# UDB5-v010.net
KiCad netlist of a schematic drawn in EAGLE
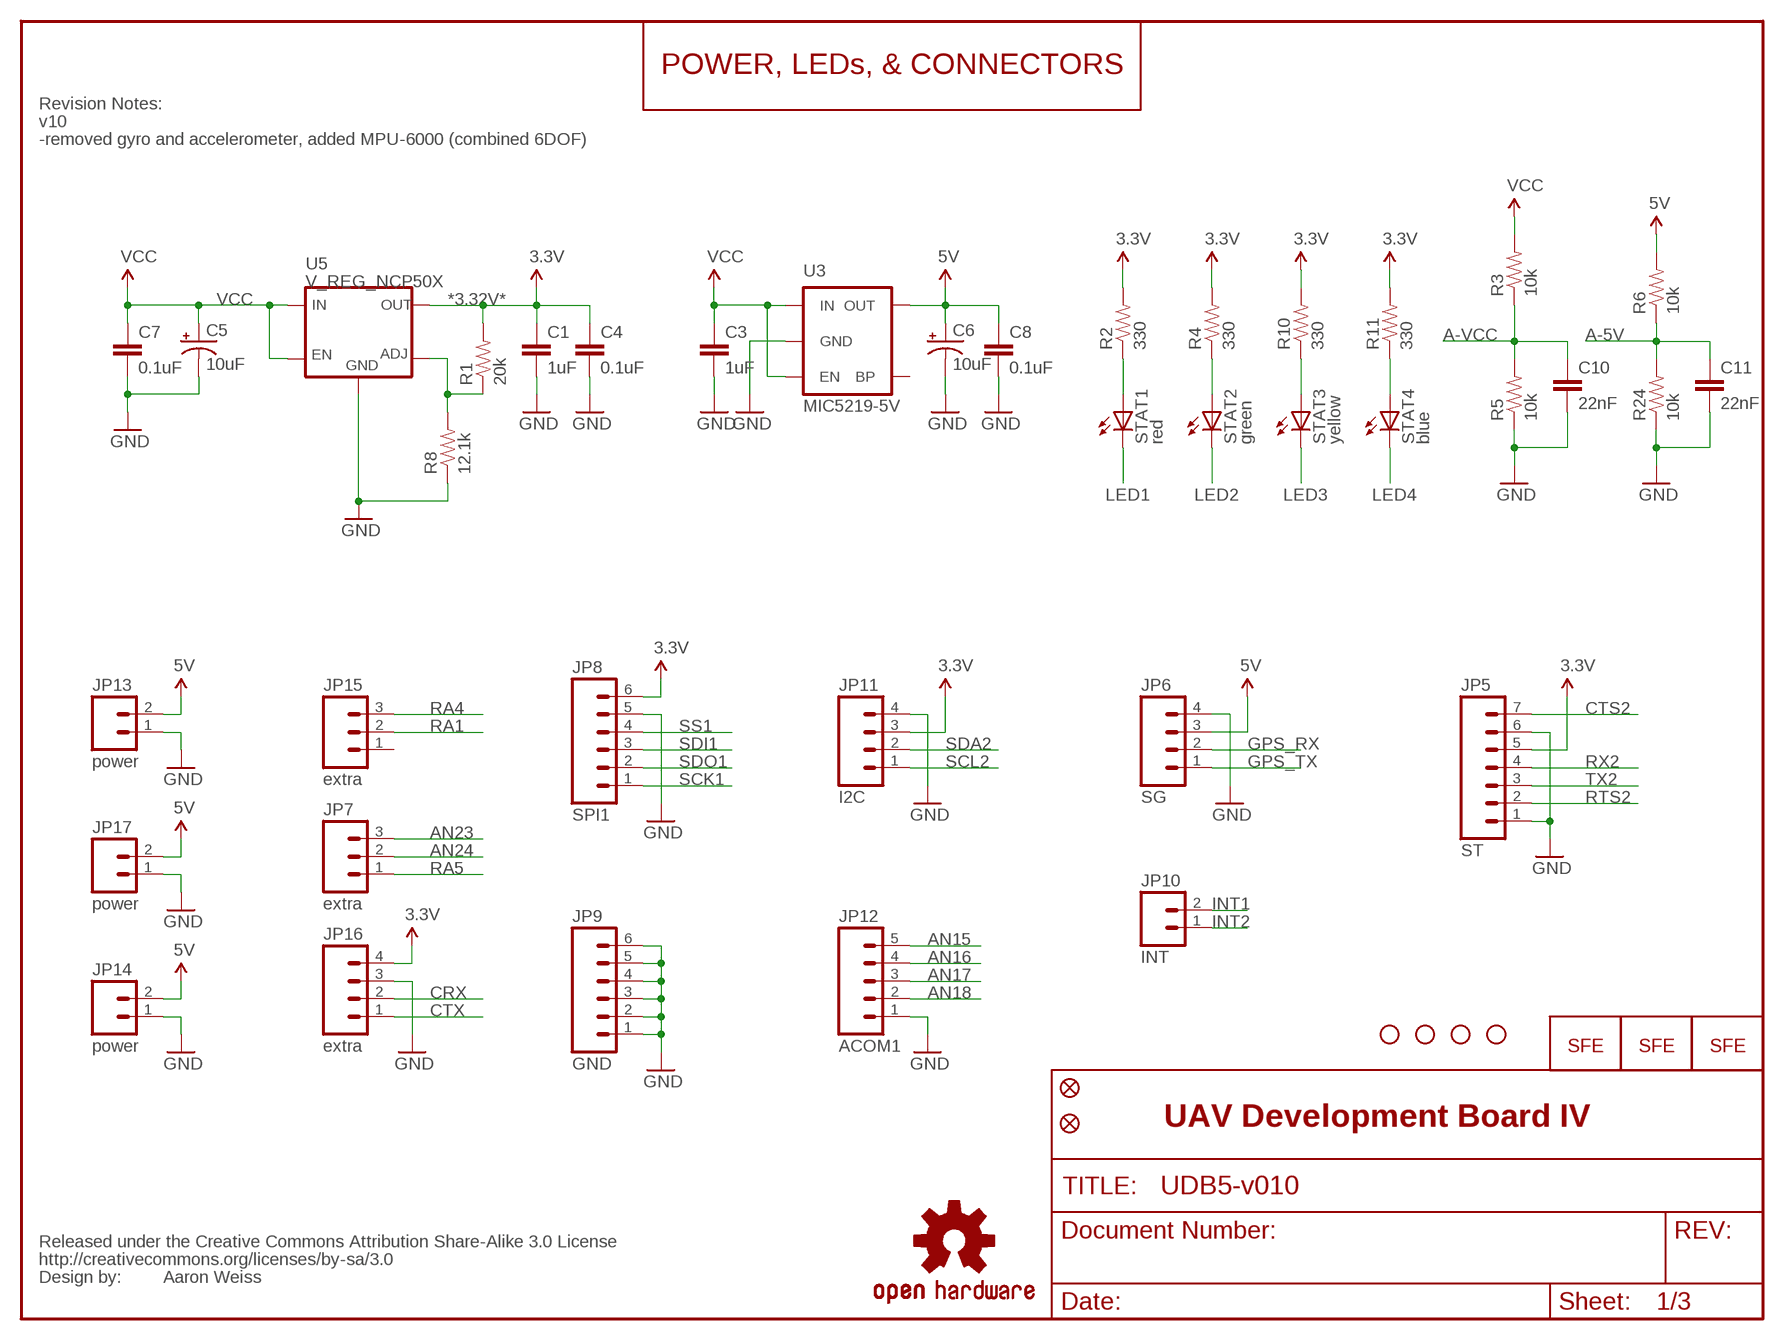
[diagram p0: schematic, sheet 1]
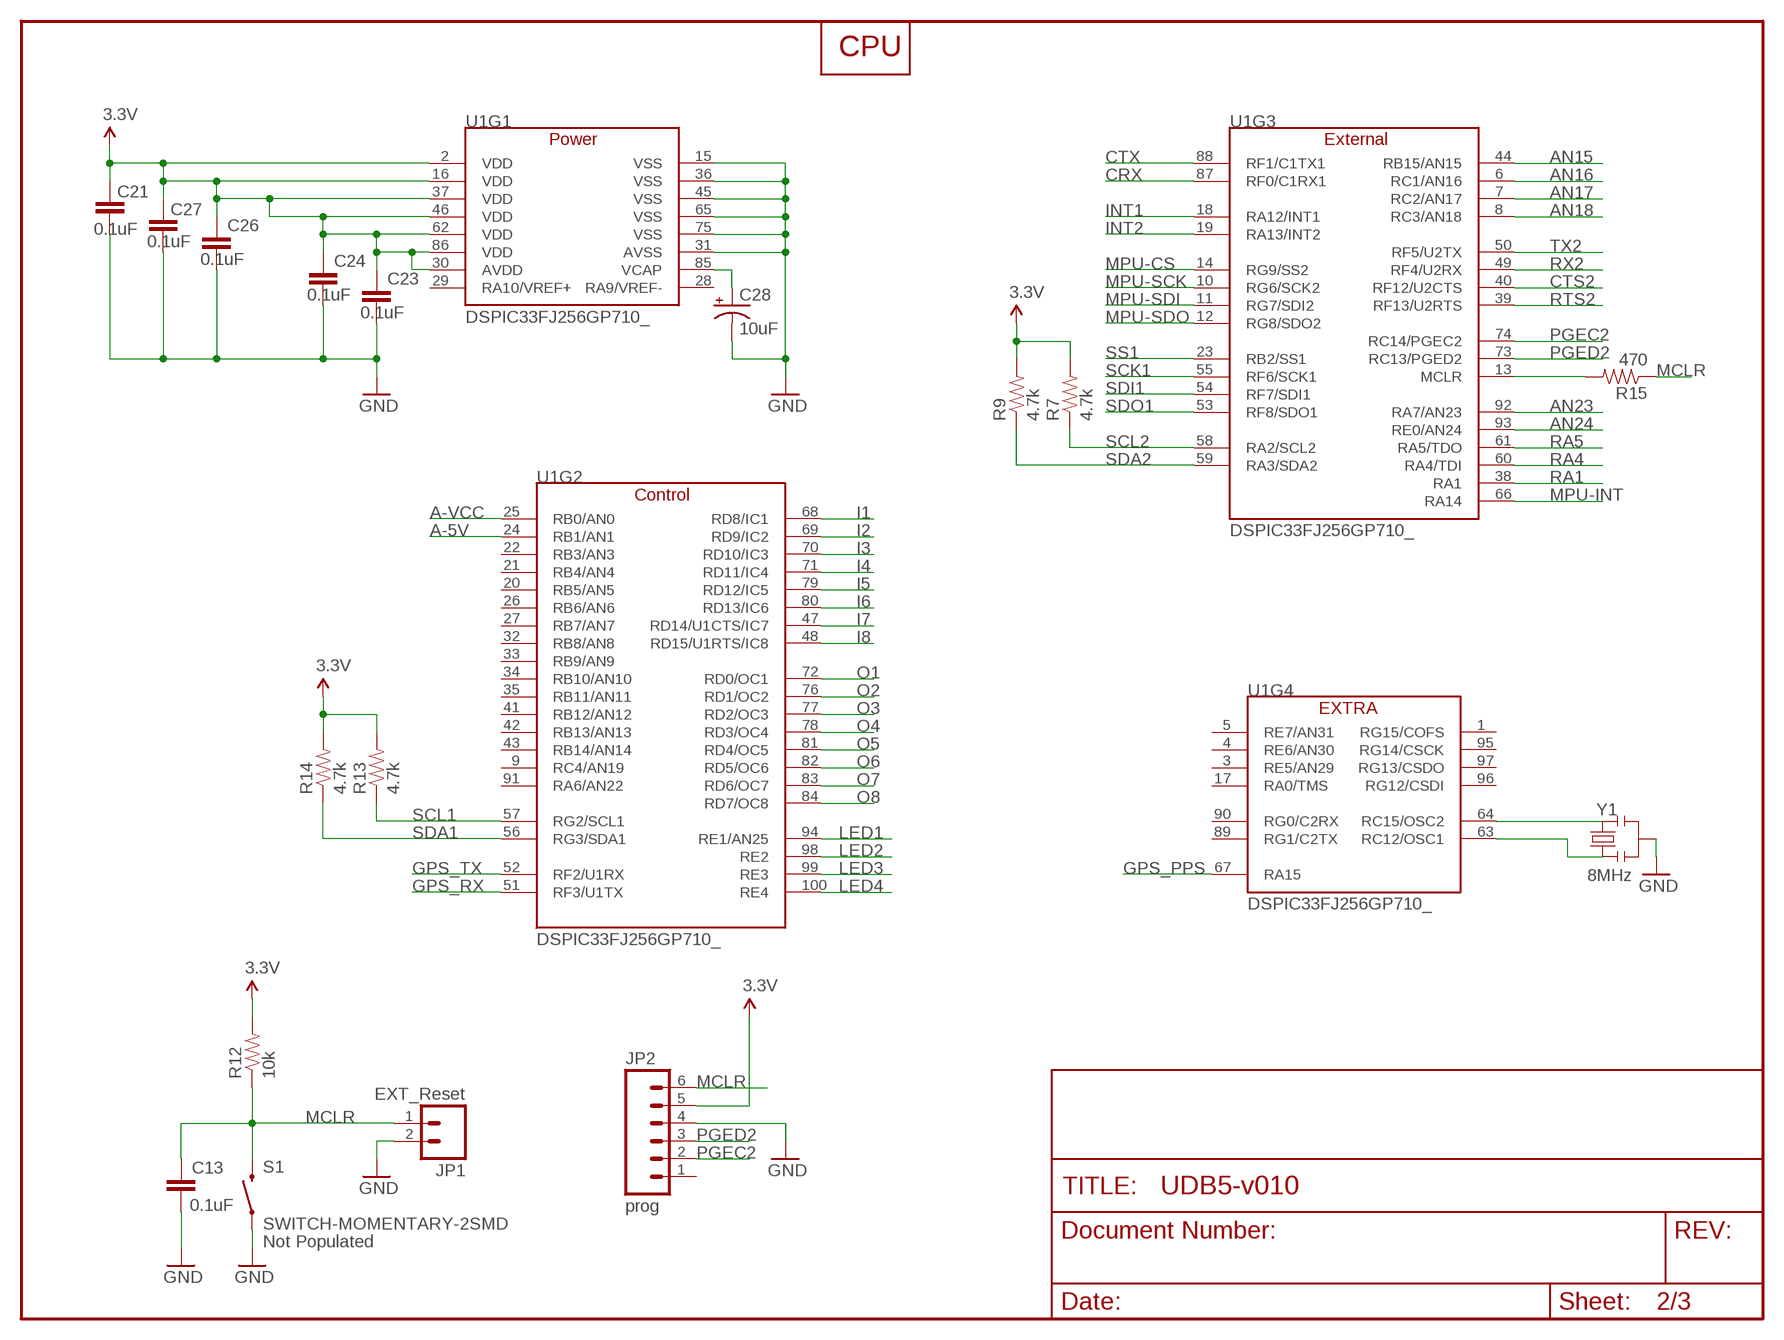
[diagram p1: schematic, sheet 2]
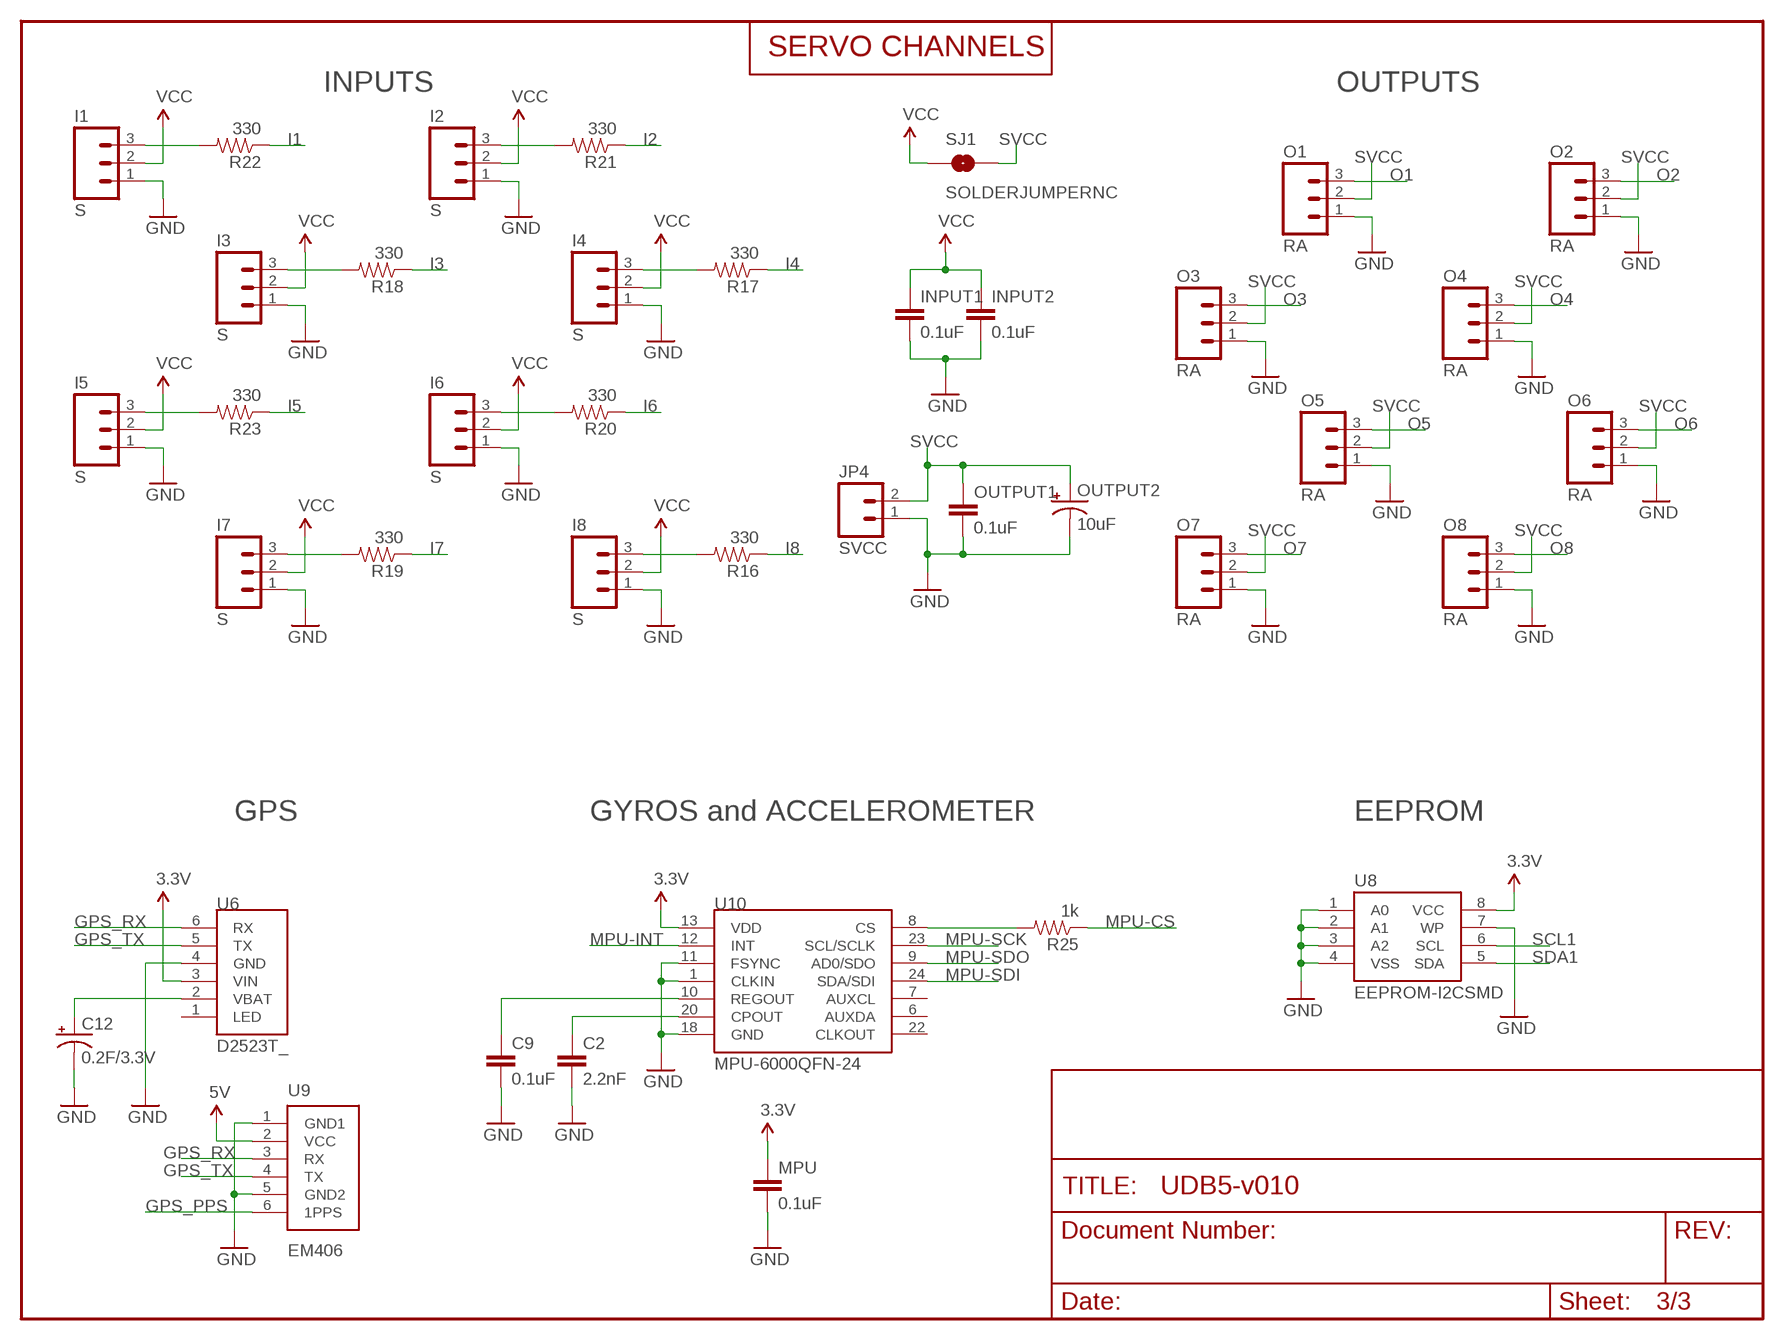
[diagram p2: schematic, sheet 3]

(export (version "E")
  (design (tool "Eeschema 10.0.6"))
  (components
    (comp (ref "C2")
      (value "2.2nF")
      (footprint "eagle-import:0402-CAP")
      (libsource (lib "eagle-import") (part "SparkFun-Capacitors_CAP0402-CAP"))
    )
    (comp (ref "C9")
      (value "0.1uF")
      (footprint "eagle-import:0402-CAP")
      (libsource (lib "eagle-import") (part "SparkFun-Capacitors_CAP0402-CAP"))
    )
    (comp (ref "C12")
      (value "0.2F/3.3V")
      (footprint "eagle-import:EN_J2")
      (libsource (lib "eagle-import") (part "SparkFun-Capacitors_CAP_POLEN_J2"))
    )
    (comp (ref "I1")
      (value "S")
      (footprint "eagle-import:1X03")
      (libsource (lib "eagle-import") (part "M03PTH"))
    )
    (comp (ref "I2")
      (value "S")
      (footprint "eagle-import:1X03")
      (libsource (lib "eagle-import") (part "M03PTH"))
    )
    (comp (ref "I3")
      (value "S")
      (footprint "eagle-import:1X03")
      (libsource (lib "eagle-import") (part "M03PTH"))
    )
    (comp (ref "I4")
      (value "S")
      (footprint "eagle-import:1X03")
      (libsource (lib "eagle-import") (part "M03PTH"))
    )
    (comp (ref "I5")
      (value "S")
      (footprint "eagle-import:1X03")
      (libsource (lib "eagle-import") (part "M03PTH"))
    )
    (comp (ref "I6")
      (value "S")
      (footprint "eagle-import:1X03")
      (libsource (lib "eagle-import") (part "M03PTH"))
    )
    (comp (ref "I7")
      (value "S")
      (footprint "eagle-import:1X03")
      (libsource (lib "eagle-import") (part "M03PTH"))
    )
    (comp (ref "I8")
      (value "S")
      (footprint "eagle-import:1X03")
      (libsource (lib "eagle-import") (part "M03PTH"))
    )
    (comp (ref "INPUT1")
      (value "0.1uF")
      (footprint "eagle-import:0402-CAP")
      (libsource (lib "eagle-import") (part "CAP0402-CAP"))
    )
    (comp (ref "INPUT2")
      (value "0.1uF")
      (footprint "eagle-import:0402-CAP")
      (libsource (lib "eagle-import") (part "CAP0402-CAP"))
    )
    (comp (ref "JP4")
      (value "SVCC")
      (footprint "eagle-import:1X02")
      (libsource (lib "eagle-import") (part "M02PTH"))
    )
    (comp (ref "MPU")
      (value "0.1uF")
      (footprint "eagle-import:0402-CAP")
      (libsource (lib "eagle-import") (part "CAP0402-CAP"))
    )
    (comp (ref "O1")
      (value "RA")
      (footprint "eagle-import:1X03")
      (libsource (lib "eagle-import") (part "M03PTH"))
    )
    (comp (ref "O2")
      (value "RA")
      (footprint "eagle-import:1X03")
      (libsource (lib "eagle-import") (part "M03PTH"))
    )
    (comp (ref "O3")
      (value "RA")
      (footprint "eagle-import:1X03")
      (libsource (lib "eagle-import") (part "M03PTH"))
    )
    (comp (ref "O4")
      (value "RA")
      (footprint "eagle-import:1X03")
      (libsource (lib "eagle-import") (part "M03PTH"))
    )
    (comp (ref "O5")
      (value "RA")
      (footprint "eagle-import:1X03")
      (libsource (lib "eagle-import") (part "M03PTH"))
    )
    (comp (ref "O6")
      (value "RA")
      (footprint "eagle-import:1X03")
      (libsource (lib "eagle-import") (part "M03PTH"))
    )
    (comp (ref "O7")
      (value "RA")
      (footprint "eagle-import:1X03")
      (libsource (lib "eagle-import") (part "M03PTH"))
    )
    (comp (ref "O8")
      (value "RA")
      (footprint "eagle-import:1X03")
      (libsource (lib "eagle-import") (part "M03PTH"))
    )
    (comp (ref "OUTPUT1")
      (value "0.1uF")
      (footprint "eagle-import:0402-CAP")
      (libsource (lib "eagle-import") (part "CAP0402-CAP"))
    )
    (comp (ref "OUTPUT2")
      (value "10uF")
      (footprint "eagle-import:EIA3216")
      (libsource (lib "eagle-import") (part "CAP_POL1206"))
    )
    (comp (ref "R16")
      (value "330")
      (footprint "eagle-import:0402-RES")
      (libsource (lib "eagle-import") (part "RESISTOR0402-RES"))
    )
    (comp (ref "R17")
      (value "330")
      (footprint "eagle-import:0402-RES")
      (libsource (lib "eagle-import") (part "RESISTOR0402-RES"))
    )
    (comp (ref "R18")
      (value "330")
      (footprint "eagle-import:0402-RES")
      (libsource (lib "eagle-import") (part "RESISTOR0402-RES"))
    )
    (comp (ref "R19")
      (value "330")
      (footprint "eagle-import:0402-RES")
      (libsource (lib "eagle-import") (part "RESISTOR0402-RES"))
    )
    (comp (ref "R20")
      (value "330")
      (footprint "eagle-import:0402-RES")
      (libsource (lib "eagle-import") (part "RESISTOR0402-RES"))
    )
    (comp (ref "R21")
      (value "330")
      (footprint "eagle-import:0402-RES")
      (libsource (lib "eagle-import") (part "RESISTOR0402-RES"))
    )
    (comp (ref "R22")
      (value "330")
      (footprint "eagle-import:0402-RES")
      (libsource (lib "eagle-import") (part "RESISTOR0402-RES"))
    )
    (comp (ref "R23")
      (value "330")
      (footprint "eagle-import:0402-RES")
      (libsource (lib "eagle-import") (part "RESISTOR0402-RES"))
    )
    (comp (ref "R25")
      (value "1k")
      (footprint "eagle-import:0402-RES")
      (libsource (lib "eagle-import") (part "RESISTOR0402-RES"))
    )
    (comp (ref "SJ1")
      (value "SOLDERJUMPERNC")
      (footprint "eagle-import:SJ_2S")
      (libsource (lib "eagle-import") (part "SOLDERJUMPERNC"))
    )
    (comp (ref "U6")
      (value "D2523T_")
      (footprint "eagle-import:EM406")
      (libsource (lib "eagle-import") (part "D2523T_"))
    )
    (comp (ref "U8")
      (value "EEPROM-I2CSMD")
      (footprint "eagle-import:SO08")
      (libsource (lib "eagle-import") (part "EEPROM-I2CSMD"))
    )
    (comp (ref "U9")
      (value "EM406")
      (footprint "eagle-import:EM406")
      (libsource (lib "eagle-import") (part "EM406"))
    )
    (comp (ref "U10")
      (value "MPU-6000QFN-24")
      (footprint "eagle-import:QFN-24-TESTING")
      (libsource (lib "eagle-import") (part "MPU-6000QFN-24"))
    )
    (comp (ref "C13")
      (value "0.1uF")
      (footprint "eagle-import:0402-CAP")
      (libsource (lib "eagle-import") (part "CAP0402-CAP"))
    )
    (comp (ref "C21")
      (value "0.1uF")
      (footprint "eagle-import:0402-CAP")
      (libsource (lib "eagle-import") (part "CAP0402-CAP"))
    )
    (comp (ref "C23")
      (value "0.1uF")
      (footprint "eagle-import:0402-CAP")
      (libsource (lib "eagle-import") (part "CAP0402-CAP"))
    )
    (comp (ref "C24")
      (value "0.1uF")
      (footprint "eagle-import:0402-CAP")
      (libsource (lib "eagle-import") (part "CAP0402-CAP"))
    )
    (comp (ref "C26")
      (value "0.1uF")
      (footprint "eagle-import:0402-CAP")
      (libsource (lib "eagle-import") (part "CAP0402-CAP"))
    )
    (comp (ref "C27")
      (value "0.1uF")
      (footprint "eagle-import:0402-CAP")
      (libsource (lib "eagle-import") (part "CAP0402-CAP"))
    )
    (comp (ref "C28")
      (value "10uF")
      (footprint "eagle-import:EIA3216")
      (libsource (lib "eagle-import") (part "CAP_POL1206"))
    )
    (comp (ref "JP1")
      (value "EXT_Reset")
      (footprint "eagle-import:1X02")
      (libsource (lib "eagle-import") (part "M02PTH"))
    )
    (comp (ref "JP2")
      (value "prog")
      (footprint "eagle-import:1X06")
      (libsource (lib "eagle-import") (part "M06SIP"))
    )
    (comp (ref "R7")
      (value "4.7k")
      (footprint "eagle-import:0402-RES")
      (libsource (lib "eagle-import") (part "RESISTOR0402-RES"))
    )
    (comp (ref "R9")
      (value "4.7k")
      (footprint "eagle-import:0402-RES")
      (libsource (lib "eagle-import") (part "RESISTOR0402-RES"))
    )
    (comp (ref "R12")
      (value "10k")
      (footprint "eagle-import:0402-RES")
      (libsource (lib "eagle-import") (part "RESISTOR0402-RES"))
    )
    (comp (ref "R13")
      (value "4.7k")
      (footprint "eagle-import:0402-RES")
      (libsource (lib "eagle-import") (part "RESISTOR0402-RES"))
    )
    (comp (ref "R14")
      (value "4.7k")
      (footprint "eagle-import:0402-RES")
      (libsource (lib "eagle-import") (part "RESISTOR0402-RES"))
    )
    (comp (ref "R15")
      (value "470")
      (footprint "eagle-import:0402-RES")
      (libsource (lib "eagle-import") (part "RESISTOR0402-RES"))
    )
    (comp (ref "S1")
      (value "SWITCH-MOMENTARY-2SMD")
      (footprint "eagle-import:TACTILE_SWITCH_SMD")
      (libsource (lib "eagle-import") (part "SWITCH-MOMENTARY-2SMD"))
    )
    (comp (ref "U1")
      (value "DSPIC33FJ256GP710_")
      (footprint "eagle-import:TQFP-100-12X12MM")
      (libsource (lib "eagle-import") (part "DSPIC33FJ256GP710_"))
    )
    (comp (ref "Y1")
      (value "RESONATORSMD")
      (footprint "eagle-import:RESONATOR-SMD")
      (libsource (lib "eagle-import") (part "RESONATORSMD"))
    )
    (comp (ref "C1")
      (value "1uF")
      (footprint "eagle-import:0402-CAP")
      (libsource (lib "eagle-import") (part "CAP0402-CAP"))
    )
    (comp (ref "C3")
      (value "1uF")
      (footprint "eagle-import:0402-CAP")
      (libsource (lib "eagle-import") (part "CAP0402-CAP"))
    )
    (comp (ref "C4")
      (value "0.1uF")
      (footprint "eagle-import:0402-CAP")
      (libsource (lib "eagle-import") (part "CAP0402-CAP"))
    )
    (comp (ref "C5")
      (value "10uF")
      (footprint "eagle-import:EIA3216")
      (libsource (lib "eagle-import") (part "CAP_POL1206"))
    )
    (comp (ref "C6")
      (value "10uF")
      (footprint "eagle-import:EIA3216")
      (libsource (lib "eagle-import") (part "CAP_POL1206"))
    )
    (comp (ref "C7")
      (value "0.1uF")
      (footprint "eagle-import:0402-CAP")
      (libsource (lib "eagle-import") (part "CAP0402-CAP"))
    )
    (comp (ref "C8")
      (value "0.1uF")
      (footprint "eagle-import:0402-CAP")
      (libsource (lib "eagle-import") (part "CAP0402-CAP"))
    )
    (comp (ref "C10")
      (value "22nF")
      (footprint "eagle-import:0402-CAP")
      (libsource (lib "eagle-import") (part "CAP0402-CAP"))
    )
    (comp (ref "C11")
      (value "22nF")
      (footprint "eagle-import:0402-CAP")
      (libsource (lib "eagle-import") (part "CAP0402-CAP"))
    )
    (comp (ref "CC_TEXT1")
      (value "CREATIVE_COMMONS")
      (footprint "eagle-import:CREATIVE_COMMONS")
      (libsource (lib "eagle-import") (part "CREATIVE_COMMONS"))
    )
    (comp (ref "JP3")
      (value "LOGO-SFENEW")
      (footprint "eagle-import:SFE-NEW-WEBLOGO")
      (libsource (lib "eagle-import") (part "LOGO-SFENEW"))
    )
    (comp (ref "JP5")
      (value "ST")
      (footprint "eagle-import:1X07")
      (libsource (lib "eagle-import") (part "M07"))
    )
    (comp (ref "JP6")
      (value "SG")
      (footprint "eagle-import:1X04")
      (libsource (lib "eagle-import") (part "M04PTH"))
    )
    (comp (ref "JP7")
      (value "extra")
      (footprint "eagle-import:1X03")
      (libsource (lib "eagle-import") (part "M03PTH"))
    )
    (comp (ref "JP8")
      (value "SPI1")
      (footprint "eagle-import:1X06")
      (libsource (lib "eagle-import") (part "M06SIP"))
    )
    (comp (ref "JP9")
      (value "GND")
      (footprint "eagle-import:1X06")
      (libsource (lib "eagle-import") (part "SparkFun-Connectors_M06SIP"))
    )
    (comp (ref "JP10")
      (value "INT")
      (footprint "eagle-import:1X02")
      (libsource (lib "eagle-import") (part "M02PTH"))
    )
    (comp (ref "JP11")
      (value "I2C")
      (footprint "eagle-import:1X04")
      (libsource (lib "eagle-import") (part "M04PTH"))
    )
    (comp (ref "JP12")
      (value "ACOM1")
      (footprint "eagle-import:1X05")
      (libsource (lib "eagle-import") (part "M05PTH"))
    )
    (comp (ref "JP13")
      (value "power")
      (footprint "eagle-import:1X02")
      (libsource (lib "eagle-import") (part "M02PTH"))
    )
    (comp (ref "JP14")
      (value "power")
      (footprint "eagle-import:1X02")
      (libsource (lib "eagle-import") (part "M02PTH"))
    )
    (comp (ref "JP15")
      (value "extra")
      (footprint "eagle-import:1X03")
      (libsource (lib "eagle-import") (part "M03PTH"))
    )
    (comp (ref "JP16")
      (value "extra")
      (footprint "eagle-import:1X04")
      (libsource (lib "eagle-import") (part "M04PTH"))
    )
    (comp (ref "JP17")
      (value "power")
      (footprint "eagle-import:1X02")
      (libsource (lib "eagle-import") (part "M02PTH"))
    )
    (comp (ref "JP18")
      (value "FIDUCIAL1X2.5")
      (footprint "eagle-import:FIDUCIAL-1X2.5")
      (libsource (lib "eagle-import") (part "FIDUCIAL1X2.5"))
    )
    (comp (ref "JP19")
      (value "FIDUCIAL1X2.5")
      (footprint "eagle-import:FIDUCIAL-1X2.5")
      (libsource (lib "eagle-import") (part "FIDUCIAL1X2.5"))
    )
    (comp (ref "LOGO1")
      (value "LOGO-SFENW2")
      (footprint "eagle-import:SFE-NEW-WEB")
      (libsource (lib "eagle-import") (part "SparkFun-Aesthetics_LOGO-SFENW2"))
    )
    (comp (ref "R1")
      (value "20k")
      (footprint "eagle-import:0402-RES")
      (libsource (lib "eagle-import") (part "RESISTOR0402-RES"))
    )
    (comp (ref "R2")
      (value "330")
      (footprint "eagle-import:0402-RES")
      (libsource (lib "eagle-import") (part "RESISTOR0402-RES"))
    )
    (comp (ref "R3")
      (value "10k")
      (footprint "eagle-import:0402-RES")
      (libsource (lib "eagle-import") (part "RESISTOR0402-RES"))
    )
    (comp (ref "R4")
      (value "330")
      (footprint "eagle-import:0402-RES")
      (libsource (lib "eagle-import") (part "RESISTOR0402-RES"))
    )
    (comp (ref "R5")
      (value "10k")
      (footprint "eagle-import:0402-RES")
      (libsource (lib "eagle-import") (part "RESISTOR0402-RES"))
    )
    (comp (ref "R6")
      (value "10k")
      (footprint "eagle-import:0402-RES")
      (libsource (lib "eagle-import") (part "RESISTOR0402-RES"))
    )
    (comp (ref "R8")
      (value "12.1k")
      (footprint "eagle-import:0402-RES")
      (libsource (lib "eagle-import") (part "RESISTOR0402-RES"))
    )
    (comp (ref "R10")
      (value "330")
      (footprint "eagle-import:0402-RES")
      (libsource (lib "eagle-import") (part "RESISTOR0402-RES"))
    )
    (comp (ref "R11")
      (value "330")
      (footprint "eagle-import:0402-RES")
      (libsource (lib "eagle-import") (part "RESISTOR0402-RES"))
    )
    (comp (ref "R24")
      (value "10k")
      (footprint "eagle-import:0402-RES")
      (libsource (lib "eagle-import") (part "RESISTOR0402-RES"))
    )
    (comp (ref "STAT1")
      (value "red")
      (footprint "eagle-import:LED-0603")
      (libsource (lib "eagle-import") (part "LED0603"))
    )
    (comp (ref "STAT2")
      (value "green")
      (footprint "eagle-import:LED-0603")
      (libsource (lib "eagle-import") (part "LED0603"))
    )
    (comp (ref "STAT3")
      (value "yellow")
      (footprint "eagle-import:LED-0603")
      (libsource (lib "eagle-import") (part "LED0603"))
    )
    (comp (ref "STAT4")
      (value "blue")
      (footprint "eagle-import:LED-0603")
      (libsource (lib "eagle-import") (part "LED0603"))
    )
    (comp (ref "U$2")
      (value "STAND-OFF")
      (footprint "eagle-import:STAND-OFF")
      (libsource (lib "eagle-import") (part "STAND-OFF"))
    )
    (comp (ref "U$3")
      (value "STAND-OFF")
      (footprint "eagle-import:STAND-OFF")
      (libsource (lib "eagle-import") (part "STAND-OFF"))
    )
    (comp (ref "U$4")
      (value "STAND-OFF")
      (footprint "eagle-import:STAND-OFF")
      (libsource (lib "eagle-import") (part "STAND-OFF"))
    )
    (comp (ref "U$5")
      (value "STAND-OFF")
      (footprint "eagle-import:STAND-OFF")
      (libsource (lib "eagle-import") (part "STAND-OFF"))
    )
    (comp (ref "U$9")
      (value "OSHW-LOGOS")
      (footprint "eagle-import:OSHW-LOGO-S")
      (libsource (lib "eagle-import") (part "OSHW-LOGOS"))
    )
    (comp (ref "U$10")
      (value "LOGO-SFESK")
      (footprint "eagle-import:SFE-LOGO-FLAME")
      (libsource (lib "eagle-import") (part "LOGO-SFESK"))
    )
    (comp (ref "U3")
      (value "V_REG_LDOSMD")
      (footprint "eagle-import:SOT23-5")
      (libsource (lib "eagle-import") (part "V_REG_LDOSMD"))
    )
    (comp (ref "U5")
      (value "V_REG_NCP50X")
      (footprint "eagle-import:DPAK-5")
      (libsource (lib "eagle-import") (part "V_REG_NCP50X"))
    )
  )
  (nets
    (net (code "1") (name "3.3V") (class "Default")
      (node (ref "C1") (pin "1") (pinfunction "1_1") (pintype "passive"))
      (node (ref "C21") (pin "1") (pinfunction "1_1") (pintype "passive"))
      (node (ref "C23") (pin "1") (pinfunction "1_1") (pintype "passive"))
      (node (ref "C24") (pin "1") (pinfunction "1_1") (pintype "passive"))
      (node (ref "C26") (pin "1") (pinfunction "1_1") (pintype "passive"))
      (node (ref "C27") (pin "1") (pinfunction "1_1") (pintype "passive"))
      (node (ref "C4") (pin "1") (pinfunction "1_1") (pintype "passive"))
      (node (ref "JP11") (pin "3") (pinfunction "3_3") (pintype "passive"))
      (node (ref "JP16") (pin "4") (pinfunction "4_4") (pintype "passive"))
      (node (ref "JP2") (pin "5") (pinfunction "5_5") (pintype "passive"))
      (node (ref "JP5") (pin "5") (pinfunction "5_5") (pintype "passive"))
      (node (ref "JP8") (pin "6") (pinfunction "6_6") (pintype "passive"))
      (node (ref "MPU") (pin "1") (pinfunction "1_1") (pintype "passive"))
      (node (ref "R1") (pin "2") (pinfunction "2_2") (pintype "passive"))
      (node (ref "R10") (pin "2") (pinfunction "2_2") (pintype "passive"))
      (node (ref "R11") (pin "2") (pinfunction "2_2") (pintype "passive"))
      (node (ref "R12") (pin "2") (pinfunction "2_2") (pintype "passive"))
      (node (ref "R13") (pin "2") (pinfunction "2_2") (pintype "passive"))
      (node (ref "R14") (pin "2") (pinfunction "2_2") (pintype "passive"))
      (node (ref "R2") (pin "2") (pinfunction "2_2") (pintype "passive"))
      (node (ref "R4") (pin "2") (pinfunction "2_2") (pintype "passive"))
      (node (ref "R7") (pin "2") (pinfunction "2_2") (pintype "passive"))
      (node (ref "R9") (pin "2") (pinfunction "2_2") (pintype "passive"))
      (node (ref "U1") (pin "16") (pinfunction "VDD_16") (pintype "bidirectional"))
      (node (ref "U1") (pin "2") (pinfunction "VDD_2") (pintype "bidirectional"))
      (node (ref "U1") (pin "30") (pinfunction "AVDD_30") (pintype "bidirectional"))
      (node (ref "U1") (pin "37") (pinfunction "VDD_37") (pintype "bidirectional"))
      (node (ref "U1") (pin "46") (pinfunction "VDD_46") (pintype "bidirectional"))
      (node (ref "U1") (pin "62") (pinfunction "VDD_62") (pintype "bidirectional"))
      (node (ref "U1") (pin "86") (pinfunction "VDD_86") (pintype "bidirectional"))
      (node (ref "U10") (pin "13") (pinfunction "VDD_13") (pintype "bidirectional"))
      (node (ref "U5") (pin "VOUT") (pinfunction "OUT_VOUT") (pintype "output"))
      (node (ref "U6") (pin "3") (pinfunction "VIN_3") (pintype "bidirectional"))
      (node (ref "U8") (pin "8") (pinfunction "VCC_8") (pintype "power_in"))
    )
    (net (code "2") (name "5V") (class "Default")
      (node (ref "C6") (pin "A") (pinfunction "+_A") (pintype "passive"))
      (node (ref "C8") (pin "1") (pinfunction "1_1") (pintype "passive"))
      (node (ref "JP13") (pin "2") (pinfunction "2_2") (pintype "passive"))
      (node (ref "JP14") (pin "2") (pinfunction "2_2") (pintype "passive"))
      (node (ref "JP17") (pin "2") (pinfunction "2_2") (pintype "passive"))
      (node (ref "JP6") (pin "3") (pinfunction "3_3") (pintype "passive"))
      (node (ref "R6") (pin "2") (pinfunction "2_2") (pintype "passive"))
      (node (ref "U3") (pin "5") (pinfunction "OUT_5") (pintype "passive"))
      (node (ref "U9") (pin "2") (pinfunction "VCC_2") (pintype "bidirectional"))
    )
    (net (code "3") (name "A-5V") (class "Default")
      (node (ref "C11") (pin "1") (pinfunction "1_1") (pintype "passive"))
      (node (ref "R24") (pin "2") (pinfunction "2_2") (pintype "passive"))
      (node (ref "R6") (pin "1") (pinfunction "1_1") (pintype "passive"))
      (node (ref "U1") (pin "24") (pinfunction "RB1/AN1_24") (pintype "bidirectional"))
    )
    (net (code "4") (name "A-VCC") (class "Default")
      (node (ref "C10") (pin "1") (pinfunction "1_1") (pintype "passive"))
      (node (ref "R3") (pin "1") (pinfunction "1_1") (pintype "passive"))
      (node (ref "R5") (pin "2") (pinfunction "2_2") (pintype "passive"))
      (node (ref "U1") (pin "25") (pinfunction "RB0/AN0_25") (pintype "bidirectional"))
    )
    (net (code "5") (name "AN15") (class "Default")
      (node (ref "JP12") (pin "5") (pinfunction "5_5") (pintype "passive"))
      (node (ref "U1") (pin "44") (pinfunction "RB15/AN15_44") (pintype "bidirectional"))
    )
    (net (code "6") (name "AN16") (class "Default")
      (node (ref "JP12") (pin "4") (pinfunction "4_4") (pintype "passive"))
      (node (ref "U1") (pin "6") (pinfunction "RC1/AN16_6") (pintype "bidirectional"))
    )
    (net (code "7") (name "AN17") (class "Default")
      (node (ref "JP12") (pin "3") (pinfunction "3_3") (pintype "passive"))
      (node (ref "U1") (pin "7") (pinfunction "RC2/AN17_7") (pintype "bidirectional"))
    )
    (net (code "8") (name "AN18") (class "Default")
      (node (ref "JP12") (pin "2") (pinfunction "2_2") (pintype "passive"))
      (node (ref "U1") (pin "8") (pinfunction "RC3/AN18_8") (pintype "bidirectional"))
    )
    (net (code "9") (name "AN23") (class "Default")
      (node (ref "JP7") (pin "3") (pinfunction "3_3") (pintype "passive"))
      (node (ref "U1") (pin "92") (pinfunction "RA7/AN23_92") (pintype "bidirectional"))
    )
    (net (code "10") (name "AN24") (class "Default")
      (node (ref "JP7") (pin "2") (pinfunction "2_2") (pintype "passive"))
      (node (ref "U1") (pin "93") (pinfunction "RE0/AN24_93") (pintype "bidirectional"))
    )
    (net (code "11") (name "CRX") (class "Default")
      (node (ref "JP16") (pin "2") (pinfunction "2_2") (pintype "passive"))
      (node (ref "U1") (pin "87") (pinfunction "RF0/C1RX1_87") (pintype "bidirectional"))
    )
    (net (code "12") (name "CTS2") (class "Default")
      (node (ref "JP5") (pin "7") (pinfunction "7_7") (pintype "passive"))
      (node (ref "U1") (pin "40") (pinfunction "RF12/U2CTS_40") (pintype "bidirectional"))
    )
    (net (code "13") (name "CTX") (class "Default")
      (node (ref "JP16") (pin "1") (pinfunction "1_1") (pintype "passive"))
      (node (ref "U1") (pin "88") (pinfunction "RF1/C1TX1_88") (pintype "bidirectional"))
    )
    (net (code "14") (name "GND") (class "Default")
      (node (ref "C1") (pin "2") (pinfunction "2_2") (pintype "passive"))
      (node (ref "C10") (pin "2") (pinfunction "2_2") (pintype "passive"))
      (node (ref "C11") (pin "2") (pinfunction "2_2") (pintype "passive"))
      (node (ref "C12") (pin "-") (pinfunction "-_-") (pintype "passive"))
      (node (ref "C13") (pin "2") (pinfunction "2_2") (pintype "passive"))
      (node (ref "C2") (pin "2") (pinfunction "2_2") (pintype "passive"))
      (node (ref "C21") (pin "2") (pinfunction "2_2") (pintype "passive"))
      (node (ref "C23") (pin "2") (pinfunction "2_2") (pintype "passive"))
      (node (ref "C24") (pin "2") (pinfunction "2_2") (pintype "passive"))
      (node (ref "C26") (pin "2") (pinfunction "2_2") (pintype "passive"))
      (node (ref "C27") (pin "2") (pinfunction "2_2") (pintype "passive"))
      (node (ref "C28") (pin "C") (pinfunction "-_C") (pintype "passive"))
      (node (ref "C3") (pin "2") (pinfunction "2_2") (pintype "passive"))
      (node (ref "C4") (pin "2") (pinfunction "2_2") (pintype "passive"))
      (node (ref "C5") (pin "C") (pinfunction "-_C") (pintype "passive"))
      (node (ref "C6") (pin "C") (pinfunction "-_C") (pintype "passive"))
      (node (ref "C7") (pin "2") (pinfunction "2_2") (pintype "passive"))
      (node (ref "C8") (pin "2") (pinfunction "2_2") (pintype "passive"))
      (node (ref "C9") (pin "2") (pinfunction "2_2") (pintype "passive"))
      (node (ref "I1") (pin "1") (pinfunction "1_1") (pintype "passive"))
      (node (ref "I2") (pin "1") (pinfunction "1_1") (pintype "passive"))
      (node (ref "I3") (pin "1") (pinfunction "1_1") (pintype "passive"))
      (node (ref "I4") (pin "1") (pinfunction "1_1") (pintype "passive"))
      (node (ref "I5") (pin "1") (pinfunction "1_1") (pintype "passive"))
      (node (ref "I6") (pin "1") (pinfunction "1_1") (pintype "passive"))
      (node (ref "I7") (pin "1") (pinfunction "1_1") (pintype "passive"))
      (node (ref "I8") (pin "1") (pinfunction "1_1") (pintype "passive"))
      (node (ref "INPUT1") (pin "2") (pinfunction "2_2") (pintype "passive"))
      (node (ref "INPUT2") (pin "2") (pinfunction "2_2") (pintype "passive"))
      (node (ref "JP1") (pin "2") (pinfunction "2_2") (pintype "passive"))
      (node (ref "JP11") (pin "4") (pinfunction "4_4") (pintype "passive"))
      (node (ref "JP12") (pin "1") (pinfunction "1_1") (pintype "passive"))
      (node (ref "JP13") (pin "1") (pinfunction "1_1") (pintype "passive"))
      (node (ref "JP14") (pin "1") (pinfunction "1_1") (pintype "passive"))
      (node (ref "JP16") (pin "3") (pinfunction "3_3") (pintype "passive"))
      (node (ref "JP17") (pin "1") (pinfunction "1_1") (pintype "passive"))
      (node (ref "JP2") (pin "4") (pinfunction "4_4") (pintype "passive"))
      (node (ref "JP4") (pin "1") (pinfunction "1_1") (pintype "passive"))
      (node (ref "JP5") (pin "1") (pinfunction "1_1") (pintype "passive"))
      (node (ref "JP5") (pin "6") (pinfunction "6_6") (pintype "passive"))
      (node (ref "JP6") (pin "4") (pinfunction "4_4") (pintype "passive"))
      (node (ref "JP8") (pin "5") (pinfunction "5_5") (pintype "passive"))
      (node (ref "JP9") (pin "1") (pinfunction "1_1") (pintype "passive"))
      (node (ref "JP9") (pin "2") (pinfunction "2_2") (pintype "passive"))
      (node (ref "JP9") (pin "3") (pinfunction "3_3") (pintype "passive"))
      (node (ref "JP9") (pin "4") (pinfunction "4_4") (pintype "passive"))
      (node (ref "JP9") (pin "5") (pinfunction "5_5") (pintype "passive"))
      (node (ref "JP9") (pin "6") (pinfunction "6_6") (pintype "passive"))
      (node (ref "MPU") (pin "2") (pinfunction "2_2") (pintype "passive"))
      (node (ref "O1") (pin "1") (pinfunction "1_1") (pintype "passive"))
      (node (ref "O2") (pin "1") (pinfunction "1_1") (pintype "passive"))
      (node (ref "O3") (pin "1") (pinfunction "1_1") (pintype "passive"))
      (node (ref "O4") (pin "1") (pinfunction "1_1") (pintype "passive"))
      (node (ref "O5") (pin "1") (pinfunction "1_1") (pintype "passive"))
      (node (ref "O6") (pin "1") (pinfunction "1_1") (pintype "passive"))
      (node (ref "O7") (pin "1") (pinfunction "1_1") (pintype "passive"))
      (node (ref "O8") (pin "1") (pinfunction "1_1") (pintype "passive"))
      (node (ref "OUTPUT1") (pin "2") (pinfunction "2_2") (pintype "passive"))
      (node (ref "OUTPUT2") (pin "C") (pinfunction "-_C") (pintype "passive"))
      (node (ref "R24") (pin "1") (pinfunction "1_1") (pintype "passive"))
      (node (ref "R5") (pin "1") (pinfunction "1_1") (pintype "passive"))
      (node (ref "R8") (pin "1") (pinfunction "1_1") (pintype "passive"))
      (node (ref "S1") (pin "1") (pinfunction "1_1") (pintype "passive"))
      (node (ref "U1") (pin "15") (pinfunction "VSS_15") (pintype "bidirectional"))
      (node (ref "U1") (pin "31") (pinfunction "AVSS_31") (pintype "bidirectional"))
      (node (ref "U1") (pin "36") (pinfunction "VSS_36") (pintype "bidirectional"))
      (node (ref "U1") (pin "45") (pinfunction "VSS_45") (pintype "bidirectional"))
      (node (ref "U1") (pin "65") (pinfunction "VSS_65") (pintype "bidirectional"))
      (node (ref "U1") (pin "75") (pinfunction "VSS_75") (pintype "bidirectional"))
      (node (ref "U10") (pin "1") (pinfunction "CLKIN_1") (pintype "bidirectional"))
      (node (ref "U10") (pin "11") (pinfunction "FSYNC_11") (pintype "bidirectional"))
      (node (ref "U10") (pin "18") (pinfunction "GND_18") (pintype "bidirectional"))
      (node (ref "U3") (pin "2") (pinfunction "GND_2") (pintype "input"))
      (node (ref "U5") (pin "GND") (pinfunction "GND_GND") (pintype "bidirectional"))
      (node (ref "U6") (pin "4") (pinfunction "GND_4") (pintype "bidirectional"))
      (node (ref "U8") (pin "1") (pinfunction "A0_1") (pintype "bidirectional"))
      (node (ref "U8") (pin "2") (pinfunction "A1_2") (pintype "bidirectional"))
      (node (ref "U8") (pin "3") (pinfunction "A2_3") (pintype "bidirectional"))
      (node (ref "U8") (pin "4") (pinfunction "VSS_4") (pintype "power_in"))
      (node (ref "U8") (pin "7") (pinfunction "WP_7") (pintype "bidirectional"))
      (node (ref "U9") (pin "1") (pinfunction "GND1_1") (pintype "bidirectional"))
      (node (ref "U9") (pin "5") (pinfunction "GND2_5") (pintype "bidirectional"))
      (node (ref "Y1") (pin "2") (pinfunction "2_2") (pintype "passive"))
    )
    (net (code "15") (name "GPS_PPS") (class "Default")
      (node (ref "U1") (pin "67") (pinfunction "RA15_67") (pintype "bidirectional"))
      (node (ref "U9") (pin "6") (pinfunction "1PPS_6") (pintype "bidirectional"))
    )
    (net (code "16") (name "GPS_RX") (class "Default")
      (node (ref "JP6") (pin "2") (pinfunction "2_2") (pintype "passive"))
      (node (ref "U1") (pin "51") (pinfunction "RF3/U1TX_51") (pintype "bidirectional"))
      (node (ref "U6") (pin "6") (pinfunction "RX_6") (pintype "bidirectional"))
      (node (ref "U9") (pin "3") (pinfunction "RX_3") (pintype "bidirectional"))
    )
    (net (code "17") (name "GPS_TX") (class "Default")
      (node (ref "JP6") (pin "1") (pinfunction "1_1") (pintype "passive"))
      (node (ref "U1") (pin "52") (pinfunction "RF2/U1RX_52") (pintype "bidirectional"))
      (node (ref "U6") (pin "5") (pinfunction "TX_5") (pintype "bidirectional"))
      (node (ref "U9") (pin "4") (pinfunction "TX_4") (pintype "bidirectional"))
    )
    (net (code "18") (name "I1") (class "Default")
      (node (ref "R22") (pin "1") (pinfunction "1_1") (pintype "passive"))
      (node (ref "U1") (pin "68") (pinfunction "RD8/IC1_68") (pintype "bidirectional"))
    )
    (net (code "19") (name "I2") (class "Default")
      (node (ref "R21") (pin "1") (pinfunction "1_1") (pintype "passive"))
      (node (ref "U1") (pin "69") (pinfunction "RD9/IC2_69") (pintype "bidirectional"))
    )
    (net (code "20") (name "I3") (class "Default")
      (node (ref "R18") (pin "1") (pinfunction "1_1") (pintype "passive"))
      (node (ref "U1") (pin "70") (pinfunction "RD10/IC3_70") (pintype "bidirectional"))
    )
    (net (code "21") (name "I4") (class "Default")
      (node (ref "R17") (pin "1") (pinfunction "1_1") (pintype "passive"))
      (node (ref "U1") (pin "71") (pinfunction "RD11/IC4_71") (pintype "bidirectional"))
    )
    (net (code "22") (name "I5") (class "Default")
      (node (ref "R23") (pin "1") (pinfunction "1_1") (pintype "passive"))
      (node (ref "U1") (pin "79") (pinfunction "RD12/IC5_79") (pintype "bidirectional"))
    )
    (net (code "23") (name "I6") (class "Default")
      (node (ref "R20") (pin "1") (pinfunction "1_1") (pintype "passive"))
      (node (ref "U1") (pin "80") (pinfunction "RD13/IC6_80") (pintype "bidirectional"))
    )
    (net (code "24") (name "I7") (class "Default")
      (node (ref "R19") (pin "1") (pinfunction "1_1") (pintype "passive"))
      (node (ref "U1") (pin "47") (pinfunction "RD14/U1CTS/IC7_47") (pintype "bidirectional"))
    )
    (net (code "25") (name "I8") (class "Default")
      (node (ref "R16") (pin "1") (pinfunction "1_1") (pintype "passive"))
      (node (ref "U1") (pin "48") (pinfunction "RD15/U1RTS/IC8_48") (pintype "bidirectional"))
    )
    (net (code "26") (name "INT1") (class "Default")
      (node (ref "JP10") (pin "2") (pinfunction "2_2") (pintype "passive"))
      (node (ref "U1") (pin "18") (pinfunction "RA12/INT1_18") (pintype "bidirectional"))
    )
    (net (code "27") (name "INT2") (class "Default")
      (node (ref "JP10") (pin "1") (pinfunction "1_1") (pintype "passive"))
      (node (ref "U1") (pin "19") (pinfunction "RA13/INT2_19") (pintype "bidirectional"))
    )
    (net (code "28") (name "LED1") (class "Default")
      (node (ref "STAT1") (pin "C") (pinfunction "C_C") (pintype "passive"))
      (node (ref "U1") (pin "94") (pinfunction "RE1/AN25_94") (pintype "bidirectional"))
    )
    (net (code "29") (name "LED2") (class "Default")
      (node (ref "STAT2") (pin "C") (pinfunction "C_C") (pintype "passive"))
      (node (ref "U1") (pin "98") (pinfunction "RE2_98") (pintype "bidirectional"))
    )
    (net (code "30") (name "LED3") (class "Default")
      (node (ref "STAT3") (pin "C") (pinfunction "C_C") (pintype "passive"))
      (node (ref "U1") (pin "99") (pinfunction "RE3_99") (pintype "bidirectional"))
    )
    (net (code "31") (name "LED4") (class "Default")
      (node (ref "STAT4") (pin "C") (pinfunction "C_C") (pintype "passive"))
      (node (ref "U1") (pin "100") (pinfunction "RE4_100") (pintype "bidirectional"))
    )
    (net (code "32") (name "MCLR") (class "Default")
      (node (ref "C13") (pin "1") (pinfunction "1_1") (pintype "passive"))
      (node (ref "JP1") (pin "1") (pinfunction "1_1") (pintype "passive"))
      (node (ref "JP2") (pin "6") (pinfunction "6_6") (pintype "passive"))
      (node (ref "R12") (pin "1") (pinfunction "1_1") (pintype "passive"))
      (node (ref "R15") (pin "1") (pinfunction "1_1") (pintype "passive"))
      (node (ref "S1") (pin "3") (pinfunction "2_3") (pintype "passive"))
    )
    (net (code "33") (name "MPU-CS") (class "Default")
      (node (ref "R25") (pin "1") (pinfunction "1_1") (pintype "passive"))
      (node (ref "U1") (pin "14") (pinfunction "RG9/SS2_14") (pintype "bidirectional"))
    )
    (net (code "34") (name "MPU-INT") (class "Default")
      (node (ref "U1") (pin "66") (pinfunction "RA14_66") (pintype "bidirectional"))
      (node (ref "U10") (pin "12") (pinfunction "INT_12") (pintype "bidirectional"))
    )
    (net (code "35") (name "MPU-SCK") (class "Default")
      (node (ref "U1") (pin "10") (pinfunction "RG6/SCK2_10") (pintype "bidirectional"))
      (node (ref "U10") (pin "23") (pinfunction "SCL/SCLK_23") (pintype "bidirectional"))
    )
    (net (code "36") (name "MPU-SDI") (class "Default")
      (node (ref "U1") (pin "11") (pinfunction "RG7/SDI2_11") (pintype "bidirectional"))
      (node (ref "U10") (pin "24") (pinfunction "SDA/SDI_24") (pintype "bidirectional"))
    )
    (net (code "37") (name "MPU-SDO") (class "Default")
      (node (ref "U1") (pin "12") (pinfunction "RG8/SDO2_12") (pintype "bidirectional"))
      (node (ref "U10") (pin "9") (pinfunction "AD0/SDO_9") (pintype "bidirectional"))
    )
    (net (code "38") (name "Net-(C28-+)") (class "Default")
      (node (ref "C28") (pin "A") (pinfunction "+_A") (pintype "passive"))
      (node (ref "U1") (pin "85") (pinfunction "VCAP_85") (pintype "bidirectional"))
    )
    (net (code "39") (name "Net-(I1-Pad3)") (class "Default")
      (node (ref "I1") (pin "3") (pinfunction "3_3") (pintype "passive"))
      (node (ref "R22") (pin "2") (pinfunction "2_2") (pintype "passive"))
    )
    (net (code "40") (name "Net-(I2-Pad3)") (class "Default")
      (node (ref "I2") (pin "3") (pinfunction "3_3") (pintype "passive"))
      (node (ref "R21") (pin "2") (pinfunction "2_2") (pintype "passive"))
    )
    (net (code "41") (name "Net-(I3-Pad3)") (class "Default")
      (node (ref "I3") (pin "3") (pinfunction "3_3") (pintype "passive"))
      (node (ref "R18") (pin "2") (pinfunction "2_2") (pintype "passive"))
    )
    (net (code "42") (name "Net-(I4-Pad3)") (class "Default")
      (node (ref "I4") (pin "3") (pinfunction "3_3") (pintype "passive"))
      (node (ref "R17") (pin "2") (pinfunction "2_2") (pintype "passive"))
    )
    (net (code "43") (name "Net-(I5-Pad3)") (class "Default")
      (node (ref "I5") (pin "3") (pinfunction "3_3") (pintype "passive"))
      (node (ref "R23") (pin "2") (pinfunction "2_2") (pintype "passive"))
    )
    (net (code "44") (name "Net-(I6-Pad3)") (class "Default")
      (node (ref "I6") (pin "3") (pinfunction "3_3") (pintype "passive"))
      (node (ref "R20") (pin "2") (pinfunction "2_2") (pintype "passive"))
    )
    (net (code "45") (name "Net-(I7-Pad3)") (class "Default")
      (node (ref "I7") (pin "3") (pinfunction "3_3") (pintype "passive"))
      (node (ref "R19") (pin "2") (pinfunction "2_2") (pintype "passive"))
    )
    (net (code "46") (name "Net-(I8-Pad3)") (class "Default")
      (node (ref "I8") (pin "3") (pinfunction "3_3") (pintype "passive"))
      (node (ref "R16") (pin "2") (pinfunction "2_2") (pintype "passive"))
    )
    (net (code "47") (name "Net-(R1-Pad1)") (class "Default")
      (node (ref "R1") (pin "1") (pinfunction "1_1") (pintype "passive"))
      (node (ref "R8") (pin "2") (pinfunction "2_2") (pintype "passive"))
      (node (ref "U5") (pin "ADJ") (pinfunction "ADJ_ADJ") (pintype "input"))
    )
    (net (code "48") (name "Net-(R2-Pad1)") (class "Default")
      (node (ref "R2") (pin "1") (pinfunction "1_1") (pintype "passive"))
      (node (ref "STAT1") (pin "A") (pinfunction "A_A") (pintype "passive"))
    )
    (net (code "49") (name "Net-(R4-Pad1)") (class "Default")
      (node (ref "R4") (pin "1") (pinfunction "1_1") (pintype "passive"))
      (node (ref "STAT2") (pin "A") (pinfunction "A_A") (pintype "passive"))
    )
    (net (code "50") (name "Net-(R10-Pad1)") (class "Default")
      (node (ref "R10") (pin "1") (pinfunction "1_1") (pintype "passive"))
      (node (ref "STAT3") (pin "A") (pinfunction "A_A") (pintype "passive"))
    )
    (net (code "51") (name "Net-(R11-Pad1)") (class "Default")
      (node (ref "R11") (pin "1") (pinfunction "1_1") (pintype "passive"))
      (node (ref "STAT4") (pin "A") (pinfunction "A_A") (pintype "passive"))
    )
    (net (code "52") (name "Net-(U1C-MCLR)") (class "Default")
      (node (ref "R15") (pin "2") (pinfunction "2_2") (pintype "passive"))
      (node (ref "U1") (pin "13") (pinfunction "MCLR_13") (pintype "bidirectional"))
    )
    (net (code "53") (name "Net-(U1D-RC12{slash}OSC1)") (class "Default")
      (node (ref "U1") (pin "63") (pinfunction "RC12/OSC1_63") (pintype "bidirectional"))
      (node (ref "Y1") (pin "1") (pinfunction "1_1") (pintype "passive"))
    )
    (net (code "54") (name "Net-(U1D-RC15{slash}OSC2)") (class "Default")
      (node (ref "U1") (pin "64") (pinfunction "RC15/OSC2_64") (pintype "bidirectional"))
      (node (ref "Y1") (pin "3") (pinfunction "3_3") (pintype "passive"))
    )
    (net (code "55") (name "Net-(U6-VBAT)") (class "Default")
      (node (ref "C12") (pin "+") (pinfunction "+_+") (pintype "passive"))
      (node (ref "U6") (pin "2") (pinfunction "VBAT_2") (pintype "bidirectional"))
    )
    (net (code "56") (name "Net-(U10-CPOUT)") (class "Default")
      (node (ref "C2") (pin "1") (pinfunction "1_1") (pintype "passive"))
      (node (ref "U10") (pin "20") (pinfunction "CPOUT_20") (pintype "bidirectional"))
    )
    (net (code "57") (name "Net-(U10-CS)") (class "Default")
      (node (ref "R25") (pin "2") (pinfunction "2_2") (pintype "passive"))
      (node (ref "U10") (pin "8") (pinfunction "CS_8") (pintype "bidirectional"))
    )
    (net (code "58") (name "Net-(U10-REGOUT)") (class "Default")
      (node (ref "C9") (pin "1") (pinfunction "1_1") (pintype "passive"))
      (node (ref "U10") (pin "10") (pinfunction "REGOUT_10") (pintype "bidirectional"))
    )
    (net (code "59") (name "O1") (class "Default")
      (node (ref "O1") (pin "3") (pinfunction "3_3") (pintype "passive"))
      (node (ref "U1") (pin "72") (pinfunction "RD0/OC1_72") (pintype "bidirectional"))
    )
    (net (code "60") (name "O2") (class "Default")
      (node (ref "O2") (pin "3") (pinfunction "3_3") (pintype "passive"))
      (node (ref "U1") (pin "76") (pinfunction "RD1/OC2_76") (pintype "bidirectional"))
    )
    (net (code "61") (name "O3") (class "Default")
      (node (ref "O3") (pin "3") (pinfunction "3_3") (pintype "passive"))
      (node (ref "U1") (pin "77") (pinfunction "RD2/OC3_77") (pintype "bidirectional"))
    )
    (net (code "62") (name "O4") (class "Default")
      (node (ref "O4") (pin "3") (pinfunction "3_3") (pintype "passive"))
      (node (ref "U1") (pin "78") (pinfunction "RD3/OC4_78") (pintype "bidirectional"))
    )
    (net (code "63") (name "O5") (class "Default")
      (node (ref "O5") (pin "3") (pinfunction "3_3") (pintype "passive"))
      (node (ref "U1") (pin "81") (pinfunction "RD4/OC5_81") (pintype "bidirectional"))
    )
    (net (code "64") (name "O6") (class "Default")
      (node (ref "O6") (pin "3") (pinfunction "3_3") (pintype "passive"))
      (node (ref "U1") (pin "82") (pinfunction "RD5/OC6_82") (pintype "bidirectional"))
    )
    (net (code "65") (name "O7") (class "Default")
      (node (ref "O7") (pin "3") (pinfunction "3_3") (pintype "passive"))
      (node (ref "U1") (pin "83") (pinfunction "RD6/OC7_83") (pintype "bidirectional"))
    )
    (net (code "66") (name "O8") (class "Default")
      (node (ref "O8") (pin "3") (pinfunction "3_3") (pintype "passive"))
      (node (ref "U1") (pin "84") (pinfunction "RD7/OC8_84") (pintype "bidirectional"))
    )
    (net (code "67") (name "PGEC2") (class "Default")
      (node (ref "JP2") (pin "2") (pinfunction "2_2") (pintype "passive"))
      (node (ref "U1") (pin "74") (pinfunction "RC14/PGEC2_74") (pintype "bidirectional"))
    )
    (net (code "68") (name "PGED2") (class "Default")
      (node (ref "JP2") (pin "3") (pinfunction "3_3") (pintype "passive"))
      (node (ref "U1") (pin "73") (pinfunction "RC13/PGED2_73") (pintype "bidirectional"))
    )
    (net (code "69") (name "RA1") (class "Default")
      (node (ref "JP15") (pin "2") (pinfunction "2_2") (pintype "passive"))
      (node (ref "U1") (pin "38") (pinfunction "RA1_38") (pintype "bidirectional"))
    )
    (net (code "70") (name "RA4") (class "Default")
      (node (ref "JP15") (pin "3") (pinfunction "3_3") (pintype "passive"))
      (node (ref "U1") (pin "60") (pinfunction "RA4/TDI_60") (pintype "bidirectional"))
    )
    (net (code "71") (name "RA5") (class "Default")
      (node (ref "JP7") (pin "1") (pinfunction "1_1") (pintype "passive"))
      (node (ref "U1") (pin "61") (pinfunction "RA5/TDO_61") (pintype "bidirectional"))
    )
    (net (code "72") (name "RTS2") (class "Default")
      (node (ref "JP5") (pin "2") (pinfunction "2_2") (pintype "passive"))
      (node (ref "U1") (pin "39") (pinfunction "RF13/U2RTS_39") (pintype "bidirectional"))
    )
    (net (code "73") (name "RX2") (class "Default")
      (node (ref "JP5") (pin "4") (pinfunction "4_4") (pintype "passive"))
      (node (ref "U1") (pin "49") (pinfunction "RF4/U2RX_49") (pintype "bidirectional"))
    )
    (net (code "74") (name "SCK1") (class "Default")
      (node (ref "JP8") (pin "1") (pinfunction "1_1") (pintype "passive"))
      (node (ref "U1") (pin "55") (pinfunction "RF6/SCK1_55") (pintype "bidirectional"))
    )
    (net (code "75") (name "SCL1") (class "Default")
      (node (ref "R13") (pin "1") (pinfunction "1_1") (pintype "passive"))
      (node (ref "U1") (pin "57") (pinfunction "RG2/SCL1_57") (pintype "bidirectional"))
      (node (ref "U8") (pin "6") (pinfunction "SCL_6") (pintype "bidirectional"))
    )
    (net (code "76") (name "SCL2") (class "Default")
      (node (ref "JP11") (pin "1") (pinfunction "1_1") (pintype "passive"))
      (node (ref "R7") (pin "1") (pinfunction "1_1") (pintype "passive"))
      (node (ref "U1") (pin "58") (pinfunction "RA2/SCL2_58") (pintype "bidirectional"))
    )
    (net (code "77") (name "SDA1") (class "Default")
      (node (ref "R14") (pin "1") (pinfunction "1_1") (pintype "passive"))
      (node (ref "U1") (pin "56") (pinfunction "RG3/SDA1_56") (pintype "bidirectional"))
      (node (ref "U8") (pin "5") (pinfunction "SDA_5") (pintype "bidirectional"))
    )
    (net (code "78") (name "SDA2") (class "Default")
      (node (ref "JP11") (pin "2") (pinfunction "2_2") (pintype "passive"))
      (node (ref "R9") (pin "1") (pinfunction "1_1") (pintype "passive"))
      (node (ref "U1") (pin "59") (pinfunction "RA3/SDA2_59") (pintype "bidirectional"))
    )
    (net (code "79") (name "SDI1") (class "Default")
      (node (ref "JP8") (pin "3") (pinfunction "3_3") (pintype "passive"))
      (node (ref "U1") (pin "54") (pinfunction "RF7/SDI1_54") (pintype "bidirectional"))
    )
    (net (code "80") (name "SDO1") (class "Default")
      (node (ref "JP8") (pin "2") (pinfunction "2_2") (pintype "passive"))
      (node (ref "U1") (pin "53") (pinfunction "RF8/SDO1_53") (pintype "bidirectional"))
    )
    (net (code "81") (name "SS1") (class "Default")
      (node (ref "JP8") (pin "4") (pinfunction "4_4") (pintype "passive"))
      (node (ref "U1") (pin "23") (pinfunction "RB2/SS1_23") (pintype "bidirectional"))
    )
    (net (code "82") (name "SVCC") (class "Default")
      (node (ref "JP4") (pin "2") (pinfunction "2_2") (pintype "passive"))
      (node (ref "O1") (pin "2") (pinfunction "2_2") (pintype "passive"))
      (node (ref "O2") (pin "2") (pinfunction "2_2") (pintype "passive"))
      (node (ref "O3") (pin "2") (pinfunction "2_2") (pintype "passive"))
      (node (ref "O4") (pin "2") (pinfunction "2_2") (pintype "passive"))
      (node (ref "O5") (pin "2") (pinfunction "2_2") (pintype "passive"))
      (node (ref "O6") (pin "2") (pinfunction "2_2") (pintype "passive"))
      (node (ref "O7") (pin "2") (pinfunction "2_2") (pintype "passive"))
      (node (ref "O8") (pin "2") (pinfunction "2_2") (pintype "passive"))
      (node (ref "OUTPUT1") (pin "1") (pinfunction "1_1") (pintype "passive"))
      (node (ref "OUTPUT2") (pin "A") (pinfunction "+_A") (pintype "passive"))
      (node (ref "SJ1") (pin "2") (pinfunction "2_2") (pintype "passive"))
    )
    (net (code "83") (name "TX2") (class "Default")
      (node (ref "JP5") (pin "3") (pinfunction "3_3") (pintype "passive"))
      (node (ref "U1") (pin "50") (pinfunction "RF5/U2TX_50") (pintype "bidirectional"))
    )
    (net (code "84") (name "VCC") (class "Default")
      (node (ref "C3") (pin "1") (pinfunction "1_1") (pintype "passive"))
      (node (ref "C5") (pin "A") (pinfunction "+_A") (pintype "passive"))
      (node (ref "C7") (pin "1") (pinfunction "1_1") (pintype "passive"))
      (node (ref "I1") (pin "2") (pinfunction "2_2") (pintype "passive"))
      (node (ref "I2") (pin "2") (pinfunction "2_2") (pintype "passive"))
      (node (ref "I3") (pin "2") (pinfunction "2_2") (pintype "passive"))
      (node (ref "I4") (pin "2") (pinfunction "2_2") (pintype "passive"))
      (node (ref "I5") (pin "2") (pinfunction "2_2") (pintype "passive"))
      (node (ref "I6") (pin "2") (pinfunction "2_2") (pintype "passive"))
      (node (ref "I7") (pin "2") (pinfunction "2_2") (pintype "passive"))
      (node (ref "I8") (pin "2") (pinfunction "2_2") (pintype "passive"))
      (node (ref "INPUT1") (pin "1") (pinfunction "1_1") (pintype "passive"))
      (node (ref "INPUT2") (pin "1") (pinfunction "1_1") (pintype "passive"))
      (node (ref "R3") (pin "2") (pinfunction "2_2") (pintype "passive"))
      (node (ref "SJ1") (pin "1") (pinfunction "1_1") (pintype "passive"))
      (node (ref "U3") (pin "1") (pinfunction "IN_1") (pintype "input"))
      (node (ref "U3") (pin "3") (pinfunction "EN_3") (pintype "input"))
      (node (ref "U5") (pin "EN") (pinfunction "EN_EN") (pintype "bidirectional"))
      (node (ref "U5") (pin "VIN") (pinfunction "IN_VIN") (pintype "input"))
    )
    (net (code "85") (name "unconnected-(JP2-Pad1)") (class "Default")
      (node (ref "JP2") (pin "1") (pinfunction "1_1") (pintype "passive"))
    )
    (net (code "86") (name "unconnected-(JP15-Pad1)") (class "Default")
      (node (ref "JP15") (pin "1") (pinfunction "1_1") (pintype "passive"))
    )
    (net (code "87") (name "unconnected-(U1A-RA9{slash}VREF--Pad28)") (class "Default")
      (node (ref "U1") (pin "28") (pinfunction "RA9/VREF-_28") (pintype "bidirectional"))
    )
    (net (code "88") (name "unconnected-(U1A-RA10{slash}VREF+-Pad29)") (class "Default")
      (node (ref "U1") (pin "29") (pinfunction "RA10/VREF+_29") (pintype "bidirectional"))
    )
    (net (code "89") (name "unconnected-(U1B-RA6{slash}AN22-Pad91)") (class "Default")
      (node (ref "U1") (pin "91") (pinfunction "RA6/AN22_91") (pintype "bidirectional"))
    )
    (net (code "90") (name "unconnected-(U1B-RB3{slash}AN3-Pad22)") (class "Default")
      (node (ref "U1") (pin "22") (pinfunction "RB3/AN3_22") (pintype "bidirectional"))
    )
    (net (code "91") (name "unconnected-(U1B-RB4{slash}AN4-Pad21)") (class "Default")
      (node (ref "U1") (pin "21") (pinfunction "RB4/AN4_21") (pintype "bidirectional"))
    )
    (net (code "92") (name "unconnected-(U1B-RB5{slash}AN5-Pad20)") (class "Default")
      (node (ref "U1") (pin "20") (pinfunction "RB5/AN5_20") (pintype "bidirectional"))
    )
    (net (code "93") (name "unconnected-(U1B-RB6{slash}AN6-Pad26)") (class "Default")
      (node (ref "U1") (pin "26") (pinfunction "RB6/AN6_26") (pintype "bidirectional"))
    )
    (net (code "94") (name "unconnected-(U1B-RB7{slash}AN7-Pad27)") (class "Default")
      (node (ref "U1") (pin "27") (pinfunction "RB7/AN7_27") (pintype "bidirectional"))
    )
    (net (code "95") (name "unconnected-(U1B-RB8{slash}AN8-Pad32)") (class "Default")
      (node (ref "U1") (pin "32") (pinfunction "RB8/AN8_32") (pintype "bidirectional"))
    )
    (net (code "96") (name "unconnected-(U1B-RB9{slash}AN9-Pad33)") (class "Default")
      (node (ref "U1") (pin "33") (pinfunction "RB9/AN9_33") (pintype "bidirectional"))
    )
    (net (code "97") (name "unconnected-(U1B-RB10{slash}AN10-Pad34)") (class "Default")
      (node (ref "U1") (pin "34") (pinfunction "RB10/AN10_34") (pintype "bidirectional"))
    )
    (net (code "98") (name "unconnected-(U1B-RB11{slash}AN11-Pad35)") (class "Default")
      (node (ref "U1") (pin "35") (pinfunction "RB11/AN11_35") (pintype "bidirectional"))
    )
    (net (code "99") (name "unconnected-(U1B-RB12{slash}AN12-Pad41)") (class "Default")
      (node (ref "U1") (pin "41") (pinfunction "RB12/AN12_41") (pintype "bidirectional"))
    )
    (net (code "100") (name "unconnected-(U1B-RB13{slash}AN13-Pad42)") (class "Default")
      (node (ref "U1") (pin "42") (pinfunction "RB13/AN13_42") (pintype "bidirectional"))
    )
    (net (code "101") (name "unconnected-(U1B-RB14{slash}AN14-Pad43)") (class "Default")
      (node (ref "U1") (pin "43") (pinfunction "RB14/AN14_43") (pintype "bidirectional"))
    )
    (net (code "102") (name "unconnected-(U1B-RC4{slash}AN19-Pad9)") (class "Default")
      (node (ref "U1") (pin "9") (pinfunction "RC4/AN19_9") (pintype "bidirectional"))
    )
    (net (code "103") (name "unconnected-(U1D-RA0{slash}TMS-Pad17)") (class "Default")
      (node (ref "U1") (pin "17") (pinfunction "RA0/TMS_17") (pintype "bidirectional"))
    )
    (net (code "104") (name "unconnected-(U1D-RE5{slash}AN29-Pad3)") (class "Default")
      (node (ref "U1") (pin "3") (pinfunction "RE5/AN29_3") (pintype "bidirectional"))
    )
    (net (code "105") (name "unconnected-(U1D-RE6{slash}AN30-Pad4)") (class "Default")
      (node (ref "U1") (pin "4") (pinfunction "RE6/AN30_4") (pintype "bidirectional"))
    )
    (net (code "106") (name "unconnected-(U1D-RE7{slash}AN31-Pad5)") (class "Default")
      (node (ref "U1") (pin "5") (pinfunction "RE7/AN31_5") (pintype "bidirectional"))
    )
    (net (code "107") (name "unconnected-(U1D-RG0{slash}C2RX-Pad90)") (class "Default")
      (node (ref "U1") (pin "90") (pinfunction "RG0/C2RX_90") (pintype "bidirectional"))
    )
    (net (code "108") (name "unconnected-(U1D-RG1{slash}C2TX-Pad89)") (class "Default")
      (node (ref "U1") (pin "89") (pinfunction "RG1/C2TX_89") (pintype "bidirectional"))
    )
    (net (code "109") (name "unconnected-(U1D-RG12{slash}CSDI-Pad96)") (class "Default")
      (node (ref "U1") (pin "96") (pinfunction "RG12/CSDI_96") (pintype "bidirectional"))
    )
    (net (code "110") (name "unconnected-(U1D-RG13{slash}CSDO-Pad97)") (class "Default")
      (node (ref "U1") (pin "97") (pinfunction "RG13/CSDO_97") (pintype "bidirectional"))
    )
    (net (code "111") (name "unconnected-(U1D-RG14{slash}CSCK-Pad95)") (class "Default")
      (node (ref "U1") (pin "95") (pinfunction "RG14/CSCK_95") (pintype "bidirectional"))
    )
    (net (code "112") (name "unconnected-(U1D-RG15{slash}COFS-Pad1)") (class "Default")
      (node (ref "U1") (pin "1") (pinfunction "RG15/COFS_1") (pintype "bidirectional"))
    )
    (net (code "113") (name "unconnected-(U3-BP-Pad4)") (class "Default")
      (node (ref "U3") (pin "4") (pinfunction "BP_4") (pintype "input"))
    )
    (net (code "114") (name "unconnected-(U6-LED-Pad1)") (class "Default")
      (node (ref "U6") (pin "1") (pinfunction "LED_1") (pintype "bidirectional"))
    )
    (net (code "115") (name "unconnected-(U10-AUXCL-Pad7)") (class "Default")
      (node (ref "U10") (pin "7") (pinfunction "AUXCL_7") (pintype "bidirectional"))
    )
    (net (code "116") (name "unconnected-(U10-AUXDA-Pad6)") (class "Default")
      (node (ref "U10") (pin "6") (pinfunction "AUXDA_6") (pintype "bidirectional"))
    )
    (net (code "117") (name "unconnected-(U10-CLKOUT-Pad22)") (class "Default")
      (node (ref "U10") (pin "22") (pinfunction "CLKOUT_22") (pintype "bidirectional"))
    )
  )
)
